# SCH_BusTemp_2026-09-07.net
KiCad netlist of a schematic drawn in EasyEDA
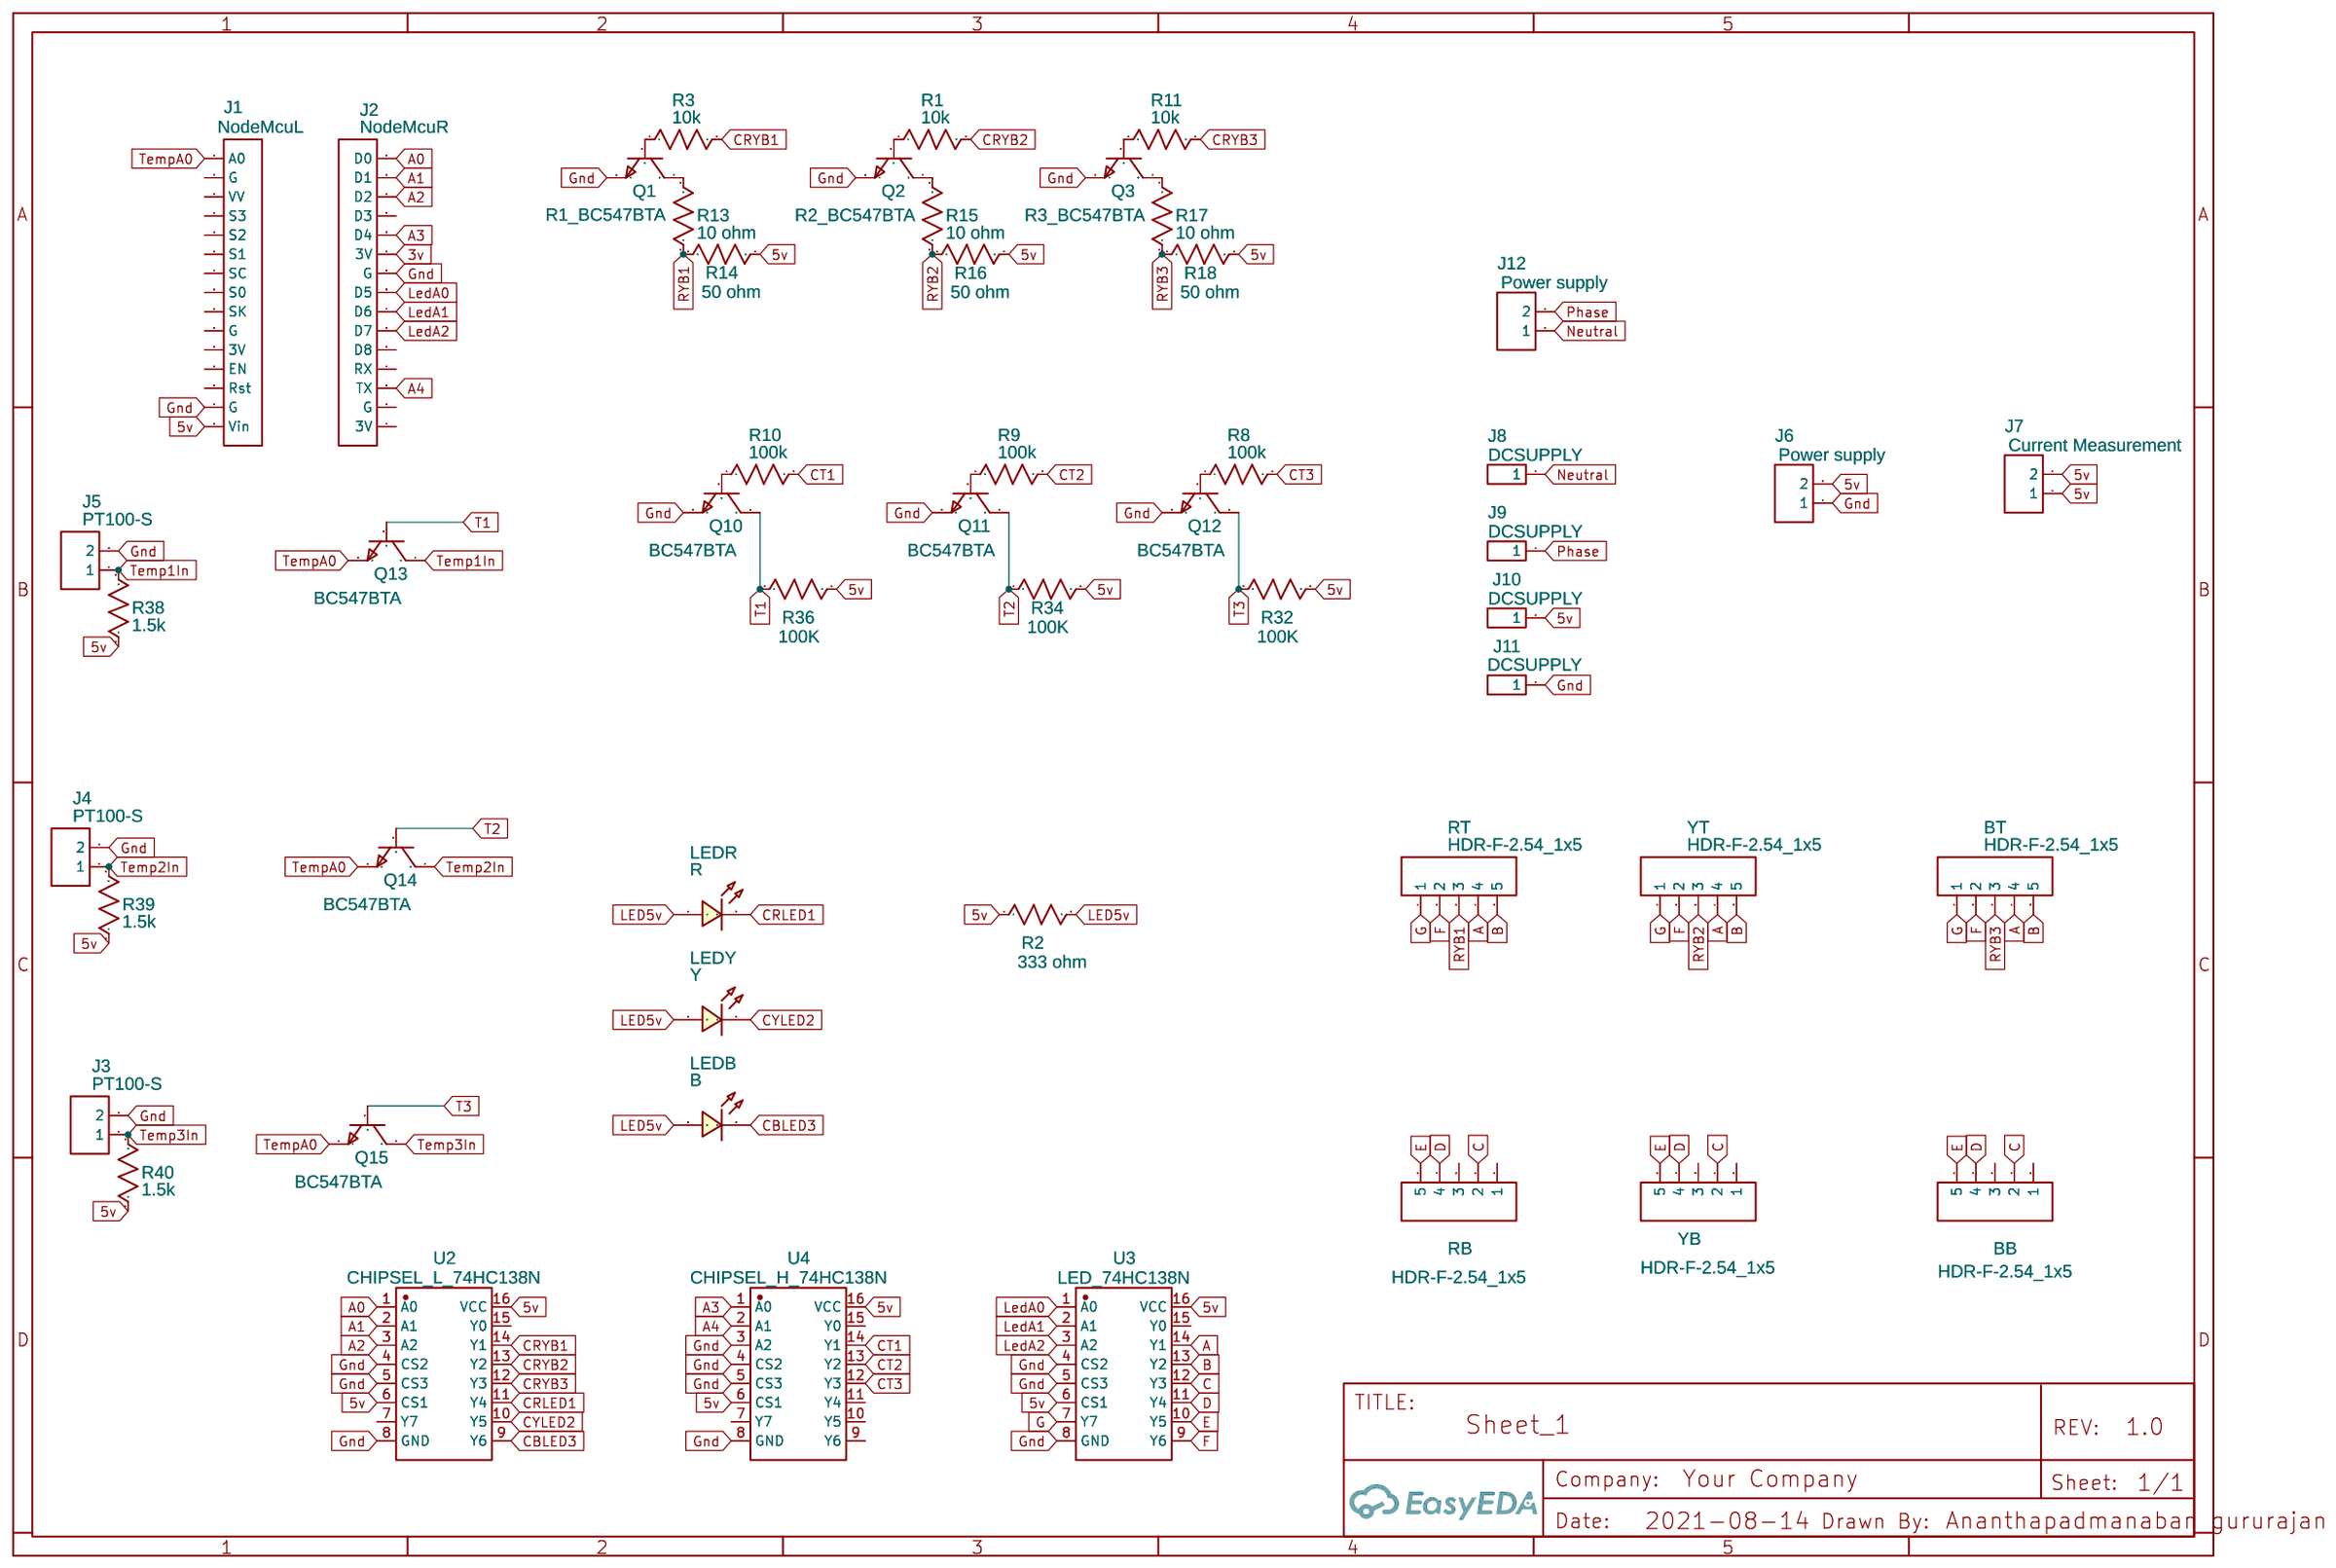
[diagram p0: schematic sheet]

(export (version "E")
  (design (tool "Eeschema 10.0.6"))
  (components
    (comp (ref "BB") (value "HDR-F-2.54_1x5") (libsource (lib "") (part "HDR-F-2.54_1x5_4")))
    (comp (ref "BT") (value "HDR-F-2.54_1x5") (libsource (lib "") (part "HDR-F-2.54_1x5_3")))
    (comp (ref "J1") (value "NodeMcuL") (libsource (lib "") (part "HDR-M-2.54_1x15_1")))
    (comp (ref "J2") (value "NodeMcuR") (libsource (lib "") (part "HDR-M-2.54_1x15")))
    (comp (ref "J3") (value "PT100-S") (libsource (lib "") (part "HDR-M-2.54_1x2")))
    (comp (ref "J4") (value "PT100-S") (libsource (lib "") (part "HDR-M-2.54_1x2")))
    (comp (ref "J5") (value "PT100-S") (libsource (lib "") (part "HDR-M-2.54_1x2")))
    (comp (ref "J6") (value "Power supply") (libsource (lib "") (part "HDR-M-2.54_1x2")))
    (comp (ref "J7") (value "Current Measurement") (libsource (lib "") (part "HDR-M-2.54_1x2")))
    (comp (ref "J8") (value "DCSUPPLY") (libsource (lib "") (part "HDR-M-2.54_1x1")))
    (comp (ref "J9") (value "DCSUPPLY") (libsource (lib "") (part "HDR-M-2.54_1x1")))
    (comp (ref "J10") (value "DCSUPPLY") (libsource (lib "") (part "HDR-M-2.54_1x1")))
    (comp (ref "J11") (value "DCSUPPLY") (libsource (lib "") (part "HDR-M-2.54_1x1")))
    (comp (ref "J12") (value "Power supply") (libsource (lib "") (part "HDR-M-2.54_1x2")))
    (comp (ref "LEDB")
      (value "B")
      (fields
        (field (name "Manufacturer Part") "204-10SUBC/S400-A4")
        (field (name "Manufacturer") "EVERLIGHT(台湾亿光)")
      )
      (libsource (lib "") (part "LED-TH-3mm_B"))
    )
    (comp (ref "LEDR")
      (value "R")
      (fields
        (field (name "Manufacturer Part") "204-10SDRD/S530-A3-L")
        (field (name "Manufacturer") "EVERLIGHT(台湾亿光)")
      )
      (libsource (lib "") (part "LED-TH-3mm_R"))
    )
    (comp (ref "LEDY")
      (value "Y")
      (fields
        (field (name "Manufacturer Part") "204-10SYGD/S530-E3")
        (field (name "Manufacturer") "EVERLIGHT(台湾亿光)")
      )
      (libsource (lib "") (part "LED-TH-3mm_G"))
    )
    (comp (ref "Q1")
      (value "R1_BC547BTA")
      (fields (field (name "Manufacturer Part") "BC547BTA") (field (name "Manufacturer") "ON Semicon"))
      (libsource (lib "") (part "BC547BTA"))
    )
    (comp (ref "Q2")
      (value "R2_BC547BTA")
      (fields (field (name "Manufacturer Part") "BC547BTA") (field (name "Manufacturer") "ON Semicon"))
      (libsource (lib "") (part "BC547BTA"))
    )
    (comp (ref "Q3")
      (value "R3_BC547BTA")
      (fields (field (name "Manufacturer Part") "BC547BTA") (field (name "Manufacturer") "ON Semicon"))
      (libsource (lib "") (part "BC547BTA"))
    )
    (comp (ref "Q10")
      (value "BC547BTA")
      (fields (field (name "Manufacturer") "ON Semicon"))
      (libsource (lib "") (part "BC547BTA"))
    )
    (comp (ref "Q11")
      (value "BC547BTA")
      (fields (field (name "Manufacturer") "ON Semicon"))
      (libsource (lib "") (part "BC547BTA"))
    )
    (comp (ref "Q12")
      (value "BC547BTA")
      (fields (field (name "Manufacturer") "ON Semicon"))
      (libsource (lib "") (part "BC547BTA"))
    )
    (comp (ref "Q13")
      (value "BC547BTA")
      (fields (field (name "Manufacturer") "ON Semicon"))
      (libsource (lib "") (part "BC547BTA"))
    )
    (comp (ref "Q14")
      (value "BC547BTA")
      (fields (field (name "Manufacturer") "ON Semicon"))
      (libsource (lib "") (part "BC547BTA"))
    )
    (comp (ref "Q15")
      (value "BC547BTA")
      (fields (field (name "Manufacturer") "ON Semicon"))
      (libsource (lib "") (part "BC547BTA"))
    )
    (comp (ref "R1") (value "10k") (libsource (lib "") (part "R_AXIAL-0.3_US")))
    (comp (ref "R2") (value "333 ohm") (libsource (lib "") (part "R_AXIAL-0.3_US")))
    (comp (ref "R3") (value "10k") (libsource (lib "") (part "R_AXIAL-0.3_US")))
    (comp (ref "R8") (value "100k") (libsource (lib "") (part "R_AXIAL-0.3_US")))
    (comp (ref "R9") (value "100k") (libsource (lib "") (part "R_AXIAL-0.3_US")))
    (comp (ref "R10") (value "100k") (libsource (lib "") (part "R_AXIAL-0.3_US")))
    (comp (ref "R11") (value "10k") (libsource (lib "") (part "R_AXIAL-0.3_US")))
    (comp (ref "R13") (value "10 ohm") (libsource (lib "") (part "R_AXIAL-0.3_US_1")))
    (comp (ref "R14") (value "50 ohm") (libsource (lib "") (part "R_AXIAL-0.3_US")))
    (comp (ref "R15") (value "10 ohm") (libsource (lib "") (part "R_AXIAL-0.3_US_1")))
    (comp (ref "R16") (value "50 ohm") (libsource (lib "") (part "R_AXIAL-0.3_US")))
    (comp (ref "R17") (value "10 ohm") (libsource (lib "") (part "R_AXIAL-0.3_US_1")))
    (comp (ref "R18") (value "50 ohm") (libsource (lib "") (part "R_AXIAL-0.3_US")))
    (comp (ref "R32") (value "100K") (libsource (lib "") (part "R_AXIAL-0.3_US")))
    (comp (ref "R34") (value "100K") (libsource (lib "") (part "R_AXIAL-0.3_US")))
    (comp (ref "R36") (value "100K") (libsource (lib "") (part "R_AXIAL-0.3_US")))
    (comp (ref "R38") (value "1.5k") (libsource (lib "") (part "R_AXIAL-0.3_US_1")))
    (comp (ref "R39") (value "1.5k") (libsource (lib "") (part "R_AXIAL-0.3_US_1")))
    (comp (ref "R40") (value "1.5k") (libsource (lib "") (part "R_AXIAL-0.3_US_1")))
    (comp (ref "RB") (value "HDR-F-2.54_1x5") (libsource (lib "") (part "HDR-F-2.54_1x5_1")))
    (comp (ref "RT") (value "HDR-F-2.54_1x5") (libsource (lib "") (part "HDR-F-2.54_1x5")))
    (comp (ref "U2")
      (value "CHIPSEL_L_74HC138N")
      (fields (field (name "Manufacturer Part") "74HC138N") (field (name "Manufacturer") "HGSEMI"))
      (libsource (lib "") (part "74HC138N"))
    )
    (comp (ref "U3")
      (value "LED_74HC138N")
      (fields (field (name "Manufacturer Part") "74HC138N") (field (name "Manufacturer") "HGSEMI"))
      (libsource (lib "") (part "74HC138N"))
    )
    (comp (ref "U4")
      (value "CHIPSEL_H_74HC138N")
      (fields (field (name "Manufacturer Part") "74HC138N") (field (name "Manufacturer") "HGSEMI"))
      (libsource (lib "") (part "74HC138N"))
    )
    (comp (ref "YB") (value "HDR-F-2.54_1x5") (libsource (lib "") (part "HDR-F-2.54_1x5_2")))
    (comp (ref "YT") (value "HDR-F-2.54_1x5") (libsource (lib "") (part "HDR-F-2.54_1x5_5")))
  )
  (nets
    (net (code "1") (name "3v") (class "Default")
      (node (ref "J2") (pin "10") (pinfunction "3V_10") (pintype "unspecified"))
    )
    (net (code "2") (name "5v") (class "Default")
      (node (ref "J1") (pin "15") (pinfunction "Vin_15") (pintype "unspecified"))
      (node (ref "J10") (pin "1") (pinfunction "1_1") (pintype "input"))
      (node (ref "J6") (pin "2") (pinfunction "2_2") (pintype "unspecified"))
      (node (ref "J7") (pin "1") (pinfunction "1_1") (pintype "unspecified"))
      (node (ref "J7") (pin "2") (pinfunction "2_2") (pintype "unspecified"))
      (node (ref "R14") (pin "2") (pinfunction "2_2") (pintype "unspecified"))
      (node (ref "R16") (pin "2") (pinfunction "2_2") (pintype "unspecified"))
      (node (ref "R18") (pin "2") (pinfunction "2_2") (pintype "unspecified"))
      (node (ref "R2") (pin "1") (pinfunction "1_1") (pintype "unspecified"))
      (node (ref "R32") (pin "2") (pinfunction "2_2") (pintype "unspecified"))
      (node (ref "R34") (pin "2") (pinfunction "2_2") (pintype "unspecified"))
      (node (ref "R36") (pin "2") (pinfunction "2_2") (pintype "unspecified"))
      (node (ref "R38") (pin "1") (pinfunction "1_1") (pintype "unspecified"))
      (node (ref "R39") (pin "1") (pinfunction "1_1") (pintype "unspecified"))
      (node (ref "R40") (pin "1") (pinfunction "1_1") (pintype "unspecified"))
      (node (ref "U2") (pin "16") (pinfunction "VCC_16") (pintype "unspecified"))
      (node (ref "U2") (pin "6") (pinfunction "CS1_6") (pintype "unspecified"))
      (node (ref "U3") (pin "16") (pinfunction "VCC_16") (pintype "unspecified"))
      (node (ref "U3") (pin "6") (pinfunction "CS1_6") (pintype "unspecified"))
      (node (ref "U4") (pin "16") (pinfunction "VCC_16") (pintype "unspecified"))
      (node (ref "U4") (pin "6") (pinfunction "CS1_6") (pintype "unspecified"))
    )
    (net (code "3") (name "A") (class "Default")
      (node (ref "BT") (pin "4") (pinfunction "4_4") (pintype "unspecified"))
      (node (ref "RT") (pin "4") (pinfunction "4_4") (pintype "unspecified"))
      (node (ref "U3") (pin "14") (pinfunction "Y1_14") (pintype "unspecified"))
      (node (ref "YT") (pin "4") (pinfunction "4_4") (pintype "unspecified"))
    )
    (net (code "4") (name "A0") (class "Default")
      (node (ref "J2") (pin "15") (pinfunction "D0_15") (pintype "unspecified"))
      (node (ref "U2") (pin "1") (pinfunction "A0_1") (pintype "unspecified"))
    )
    (net (code "5") (name "A1") (class "Default")
      (node (ref "J2") (pin "14") (pinfunction "D1_14") (pintype "unspecified"))
      (node (ref "U2") (pin "2") (pinfunction "A1_2") (pintype "unspecified"))
    )
    (net (code "6") (name "A2") (class "Default")
      (node (ref "J2") (pin "13") (pinfunction "D2_13") (pintype "unspecified"))
      (node (ref "U2") (pin "3") (pinfunction "A2_3") (pintype "unspecified"))
    )
    (net (code "7") (name "A3") (class "Default")
      (node (ref "J2") (pin "11") (pinfunction "D4_11") (pintype "unspecified"))
      (node (ref "U4") (pin "1") (pinfunction "A0_1") (pintype "unspecified"))
    )
    (net (code "8") (name "A4") (class "Default")
      (node (ref "J2") (pin "3") (pinfunction "TX_3") (pintype "unspecified"))
      (node (ref "U4") (pin "2") (pinfunction "A1_2") (pintype "unspecified"))
    )
    (net (code "9") (name "B") (class "Default")
      (node (ref "BT") (pin "5") (pinfunction "5_5") (pintype "unspecified"))
      (node (ref "RT") (pin "5") (pinfunction "5_5") (pintype "unspecified"))
      (node (ref "U3") (pin "13") (pinfunction "Y2_13") (pintype "unspecified"))
      (node (ref "YT") (pin "5") (pinfunction "5_5") (pintype "unspecified"))
    )
    (net (code "10") (name "C") (class "Default")
      (node (ref "BB") (pin "2") (pinfunction "2_2") (pintype "unspecified"))
      (node (ref "RB") (pin "2") (pinfunction "2_2") (pintype "unspecified"))
      (node (ref "U3") (pin "12") (pinfunction "Y3_12") (pintype "unspecified"))
      (node (ref "YB") (pin "2") (pinfunction "2_2") (pintype "unspecified"))
    )
    (net (code "11") (name "CBLED3") (class "Default")
      (node (ref "LEDB") (pin "2") (pinfunction "2_2") (pintype "unspecified"))
      (node (ref "U2") (pin "9") (pinfunction "Y6_9") (pintype "unspecified"))
    )
    (net (code "12") (name "CRLED1") (class "Default")
      (node (ref "LEDR") (pin "2") (pinfunction "2_2") (pintype "unspecified"))
      (node (ref "U2") (pin "11") (pinfunction "Y4_11") (pintype "unspecified"))
    )
    (net (code "13") (name "CRYB1") (class "Default")
      (node (ref "R3") (pin "2") (pinfunction "2_2") (pintype "unspecified"))
      (node (ref "U2") (pin "14") (pinfunction "Y1_14") (pintype "unspecified"))
    )
    (net (code "14") (name "CRYB2") (class "Default")
      (node (ref "R1") (pin "2") (pinfunction "2_2") (pintype "unspecified"))
      (node (ref "U2") (pin "13") (pinfunction "Y2_13") (pintype "unspecified"))
    )
    (net (code "15") (name "CRYB3") (class "Default")
      (node (ref "R11") (pin "2") (pinfunction "2_2") (pintype "unspecified"))
      (node (ref "U2") (pin "12") (pinfunction "Y3_12") (pintype "unspecified"))
    )
    (net (code "16") (name "CT1") (class "Default")
      (node (ref "R10") (pin "2") (pinfunction "2_2") (pintype "unspecified"))
      (node (ref "U4") (pin "14") (pinfunction "Y1_14") (pintype "unspecified"))
    )
    (net (code "17") (name "CT2") (class "Default")
      (node (ref "R9") (pin "2") (pinfunction "2_2") (pintype "unspecified"))
      (node (ref "U4") (pin "13") (pinfunction "Y2_13") (pintype "unspecified"))
    )
    (net (code "18") (name "CT3") (class "Default")
      (node (ref "R8") (pin "2") (pinfunction "2_2") (pintype "unspecified"))
      (node (ref "U4") (pin "12") (pinfunction "Y3_12") (pintype "unspecified"))
    )
    (net (code "19") (name "CYLED2") (class "Default")
      (node (ref "LEDY") (pin "2") (pinfunction "2_2") (pintype "unspecified"))
      (node (ref "U2") (pin "10") (pinfunction "Y5_10") (pintype "unspecified"))
    )
    (net (code "20") (name "D") (class "Default")
      (node (ref "BB") (pin "4") (pinfunction "4_4") (pintype "unspecified"))
      (node (ref "RB") (pin "4") (pinfunction "4_4") (pintype "unspecified"))
      (node (ref "U3") (pin "11") (pinfunction "Y4_11") (pintype "unspecified"))
      (node (ref "YB") (pin "4") (pinfunction "4_4") (pintype "unspecified"))
    )
    (net (code "21") (name "E") (class "Default")
      (node (ref "BB") (pin "5") (pinfunction "5_5") (pintype "unspecified"))
      (node (ref "RB") (pin "5") (pinfunction "5_5") (pintype "unspecified"))
      (node (ref "U3") (pin "10") (pinfunction "Y5_10") (pintype "unspecified"))
      (node (ref "YB") (pin "5") (pinfunction "5_5") (pintype "unspecified"))
    )
    (net (code "22") (name "F") (class "Default")
      (node (ref "BT") (pin "2") (pinfunction "2_2") (pintype "unspecified"))
      (node (ref "RT") (pin "2") (pinfunction "2_2") (pintype "unspecified"))
      (node (ref "U3") (pin "9") (pinfunction "Y6_9") (pintype "unspecified"))
      (node (ref "YT") (pin "2") (pinfunction "2_2") (pintype "unspecified"))
    )
    (net (code "23") (name "G") (class "Default")
      (node (ref "BT") (pin "1") (pinfunction "1_1") (pintype "unspecified"))
      (node (ref "RT") (pin "1") (pinfunction "1_1") (pintype "unspecified"))
      (node (ref "U3") (pin "7") (pinfunction "Y7_7") (pintype "unspecified"))
      (node (ref "YT") (pin "1") (pinfunction "1_1") (pintype "unspecified"))
    )
    (net (code "24") (name "Gnd") (class "Default")
      (node (ref "J1") (pin "14") (pinfunction "G_14") (pintype "unspecified"))
      (node (ref "J11") (pin "1") (pinfunction "1_1") (pintype "input"))
      (node (ref "J2") (pin "9") (pinfunction "G_9") (pintype "unspecified"))
      (node (ref "J3") (pin "2") (pinfunction "2_2") (pintype "unspecified"))
      (node (ref "J4") (pin "2") (pinfunction "2_2") (pintype "unspecified"))
      (node (ref "J5") (pin "2") (pinfunction "2_2") (pintype "unspecified"))
      (node (ref "J6") (pin "1") (pinfunction "1_1") (pintype "unspecified"))
      (node (ref "Q1") (pin "3") (pinfunction "E_3") (pintype "unspecified"))
      (node (ref "Q10") (pin "3") (pinfunction "E_3") (pintype "unspecified"))
      (node (ref "Q11") (pin "3") (pinfunction "E_3") (pintype "unspecified"))
      (node (ref "Q12") (pin "3") (pinfunction "E_3") (pintype "unspecified"))
      (node (ref "Q2") (pin "3") (pinfunction "E_3") (pintype "unspecified"))
      (node (ref "Q3") (pin "3") (pinfunction "E_3") (pintype "unspecified"))
      (node (ref "U2") (pin "4") (pinfunction "CS2_4") (pintype "unspecified"))
      (node (ref "U2") (pin "5") (pinfunction "CS3_5") (pintype "unspecified"))
      (node (ref "U2") (pin "8") (pinfunction "GND_8") (pintype "unspecified"))
      (node (ref "U3") (pin "4") (pinfunction "CS2_4") (pintype "unspecified"))
      (node (ref "U3") (pin "5") (pinfunction "CS3_5") (pintype "unspecified"))
      (node (ref "U3") (pin "8") (pinfunction "GND_8") (pintype "unspecified"))
      (node (ref "U4") (pin "3") (pinfunction "A2_3") (pintype "unspecified"))
      (node (ref "U4") (pin "4") (pinfunction "CS2_4") (pintype "unspecified"))
      (node (ref "U4") (pin "5") (pinfunction "CS3_5") (pintype "unspecified"))
      (node (ref "U4") (pin "8") (pinfunction "GND_8") (pintype "unspecified"))
    )
    (net (code "25") (name "LED5v") (class "Default")
      (node (ref "LEDB") (pin "1") (pinfunction "1_1") (pintype "unspecified"))
      (node (ref "LEDR") (pin "1") (pinfunction "1_1") (pintype "unspecified"))
      (node (ref "LEDY") (pin "1") (pinfunction "1_1") (pintype "unspecified"))
      (node (ref "R2") (pin "2") (pinfunction "2_2") (pintype "unspecified"))
    )
    (net (code "26") (name "LedA0") (class "Default")
      (node (ref "J2") (pin "8") (pinfunction "D5_8") (pintype "unspecified"))
      (node (ref "U3") (pin "1") (pinfunction "A0_1") (pintype "unspecified"))
    )
    (net (code "27") (name "LedA1") (class "Default")
      (node (ref "J2") (pin "7") (pinfunction "D6_7") (pintype "unspecified"))
      (node (ref "U3") (pin "2") (pinfunction "A1_2") (pintype "unspecified"))
    )
    (net (code "28") (name "LedA2") (class "Default")
      (node (ref "J2") (pin "6") (pinfunction "D7_6") (pintype "unspecified"))
      (node (ref "U3") (pin "3") (pinfunction "A2_3") (pintype "unspecified"))
    )
    (net (code "29") (name "Net-(Q1-B)") (class "Default")
      (node (ref "Q1") (pin "2") (pinfunction "B_2") (pintype "unspecified"))
      (node (ref "R3") (pin "1") (pinfunction "1_1") (pintype "unspecified"))
    )
    (net (code "30") (name "Net-(Q1-C)") (class "Default")
      (node (ref "Q1") (pin "1") (pinfunction "C_1") (pintype "unspecified"))
      (node (ref "R13") (pin "2") (pinfunction "2_2") (pintype "unspecified"))
    )
    (net (code "31") (name "Net-(Q2-B)") (class "Default")
      (node (ref "Q2") (pin "2") (pinfunction "B_2") (pintype "unspecified"))
      (node (ref "R1") (pin "1") (pinfunction "1_1") (pintype "unspecified"))
    )
    (net (code "32") (name "Net-(Q2-C)") (class "Default")
      (node (ref "Q2") (pin "1") (pinfunction "C_1") (pintype "unspecified"))
      (node (ref "R15") (pin "2") (pinfunction "2_2") (pintype "unspecified"))
    )
    (net (code "33") (name "Net-(Q3-B)") (class "Default")
      (node (ref "Q3") (pin "2") (pinfunction "B_2") (pintype "unspecified"))
      (node (ref "R11") (pin "1") (pinfunction "1_1") (pintype "unspecified"))
    )
    (net (code "34") (name "Net-(Q3-C)") (class "Default")
      (node (ref "Q3") (pin "1") (pinfunction "C_1") (pintype "unspecified"))
      (node (ref "R17") (pin "2") (pinfunction "2_2") (pintype "unspecified"))
    )
    (net (code "35") (name "Net-(Q10-B)") (class "Default")
      (node (ref "Q10") (pin "2") (pinfunction "B_2") (pintype "unspecified"))
      (node (ref "R10") (pin "1") (pinfunction "1_1") (pintype "unspecified"))
    )
    (net (code "36") (name "Net-(Q11-B)") (class "Default")
      (node (ref "Q11") (pin "2") (pinfunction "B_2") (pintype "unspecified"))
      (node (ref "R9") (pin "1") (pinfunction "1_1") (pintype "unspecified"))
    )
    (net (code "37") (name "Net-(Q12-B)") (class "Default")
      (node (ref "Q12") (pin "2") (pinfunction "B_2") (pintype "unspecified"))
      (node (ref "R8") (pin "1") (pinfunction "1_1") (pintype "unspecified"))
    )
    (net (code "38") (name "Neutral") (class "Default")
      (node (ref "J12") (pin "1") (pinfunction "1_1") (pintype "unspecified"))
      (node (ref "J8") (pin "1") (pinfunction "1_1") (pintype "input"))
    )
    (net (code "39") (name "Phase") (class "Default")
      (node (ref "J12") (pin "2") (pinfunction "2_2") (pintype "unspecified"))
      (node (ref "J9") (pin "1") (pinfunction "1_1") (pintype "input"))
    )
    (net (code "40") (name "RYB1") (class "Default")
      (node (ref "R13") (pin "1") (pinfunction "1_1") (pintype "unspecified"))
      (node (ref "R14") (pin "1") (pinfunction "1_1") (pintype "unspecified"))
      (node (ref "RT") (pin "3") (pinfunction "3_3") (pintype "unspecified"))
    )
    (net (code "41") (name "RYB2") (class "Default")
      (node (ref "R15") (pin "1") (pinfunction "1_1") (pintype "unspecified"))
      (node (ref "R16") (pin "1") (pinfunction "1_1") (pintype "unspecified"))
      (node (ref "YT") (pin "3") (pinfunction "3_3") (pintype "unspecified"))
    )
    (net (code "42") (name "RYB3") (class "Default")
      (node (ref "BT") (pin "3") (pinfunction "3_3") (pintype "unspecified"))
      (node (ref "R17") (pin "1") (pinfunction "1_1") (pintype "unspecified"))
      (node (ref "R18") (pin "1") (pinfunction "1_1") (pintype "unspecified"))
    )
    (net (code "43") (name "T1") (class "Default")
      (node (ref "Q10") (pin "1") (pinfunction "C_1") (pintype "unspecified"))
      (node (ref "Q13") (pin "2") (pinfunction "B_2") (pintype "unspecified"))
      (node (ref "R36") (pin "1") (pinfunction "1_1") (pintype "unspecified"))
    )
    (net (code "44") (name "T2") (class "Default")
      (node (ref "Q11") (pin "1") (pinfunction "C_1") (pintype "unspecified"))
      (node (ref "Q14") (pin "2") (pinfunction "B_2") (pintype "unspecified"))
      (node (ref "R34") (pin "1") (pinfunction "1_1") (pintype "unspecified"))
    )
    (net (code "45") (name "T3") (class "Default")
      (node (ref "Q12") (pin "1") (pinfunction "C_1") (pintype "unspecified"))
      (node (ref "Q15") (pin "2") (pinfunction "B_2") (pintype "unspecified"))
      (node (ref "R32") (pin "1") (pinfunction "1_1") (pintype "unspecified"))
    )
    (net (code "46") (name "Temp1In") (class "Default")
      (node (ref "J5") (pin "1") (pinfunction "1_1") (pintype "unspecified"))
      (node (ref "Q13") (pin "1") (pinfunction "C_1") (pintype "unspecified"))
      (node (ref "R38") (pin "2") (pinfunction "2_2") (pintype "unspecified"))
    )
    (net (code "47") (name "Temp2In") (class "Default")
      (node (ref "J4") (pin "1") (pinfunction "1_1") (pintype "unspecified"))
      (node (ref "Q14") (pin "1") (pinfunction "C_1") (pintype "unspecified"))
      (node (ref "R39") (pin "2") (pinfunction "2_2") (pintype "unspecified"))
    )
    (net (code "48") (name "Temp3In") (class "Default")
      (node (ref "J3") (pin "1") (pinfunction "1_1") (pintype "unspecified"))
      (node (ref "Q15") (pin "1") (pinfunction "C_1") (pintype "unspecified"))
      (node (ref "R40") (pin "2") (pinfunction "2_2") (pintype "unspecified"))
    )
    (net (code "49") (name "TempA0") (class "Default")
      (node (ref "J1") (pin "1") (pinfunction "A0_1") (pintype "unspecified"))
      (node (ref "Q13") (pin "3") (pinfunction "E_3") (pintype "unspecified"))
      (node (ref "Q14") (pin "3") (pinfunction "E_3") (pintype "unspecified"))
      (node (ref "Q15") (pin "3") (pinfunction "E_3") (pintype "unspecified"))
    )
    (net (code "50") (name "unconnected-(BB-Pad1)") (class "Default")
      (node (ref "BB") (pin "1") (pinfunction "1_1") (pintype "unspecified"))
    )
    (net (code "51") (name "unconnected-(BB-Pad3)") (class "Default")
      (node (ref "BB") (pin "3") (pinfunction "3_3") (pintype "unspecified"))
    )
    (net (code "52") (name "unconnected-(J1-3V-Pad11)") (class "Default")
      (node (ref "J1") (pin "11") (pinfunction "3V_11") (pintype "unspecified"))
    )
    (net (code "53") (name "unconnected-(J1-EN-Pad12)") (class "Default")
      (node (ref "J1") (pin "12") (pinfunction "EN_12") (pintype "unspecified"))
    )
    (net (code "54") (name "unconnected-(J1-G-Pad2)") (class "Default")
      (node (ref "J1") (pin "2") (pinfunction "G_2") (pintype "unspecified"))
    )
    (net (code "55") (name "unconnected-(J1-G-Pad10)") (class "Default")
      (node (ref "J1") (pin "10") (pinfunction "G_10") (pintype "unspecified"))
    )
    (net (code "56") (name "unconnected-(J1-Rst-Pad13)") (class "Default")
      (node (ref "J1") (pin "13") (pinfunction "Rst_13") (pintype "unspecified"))
    )
    (net (code "57") (name "unconnected-(J1-S0-Pad8)") (class "Default")
      (node (ref "J1") (pin "8") (pinfunction "S0_8") (pintype "unspecified"))
    )
    (net (code "58") (name "unconnected-(J1-S1-Pad6)") (class "Default")
      (node (ref "J1") (pin "6") (pinfunction "S1_6") (pintype "unspecified"))
    )
    (net (code "59") (name "unconnected-(J1-S2-Pad5)") (class "Default")
      (node (ref "J1") (pin "5") (pinfunction "S2_5") (pintype "unspecified"))
    )
    (net (code "60") (name "unconnected-(J1-S3-Pad4)") (class "Default")
      (node (ref "J1") (pin "4") (pinfunction "S3_4") (pintype "unspecified"))
    )
    (net (code "61") (name "unconnected-(J1-SC-Pad7)") (class "Default")
      (node (ref "J1") (pin "7") (pinfunction "SC_7") (pintype "unspecified"))
    )
    (net (code "62") (name "unconnected-(J1-SK-Pad9)") (class "Default")
      (node (ref "J1") (pin "9") (pinfunction "SK_9") (pintype "unspecified"))
    )
    (net (code "63") (name "unconnected-(J1-VV-Pad3)") (class "Default")
      (node (ref "J1") (pin "3") (pinfunction "VV_3") (pintype "unspecified"))
    )
    (net (code "64") (name "unconnected-(J2-3V-Pad1)") (class "Default")
      (node (ref "J2") (pin "1") (pinfunction "3V_1") (pintype "unspecified"))
    )
    (net (code "65") (name "unconnected-(J2-D3-Pad12)") (class "Default")
      (node (ref "J2") (pin "12") (pinfunction "D3_12") (pintype "unspecified"))
    )
    (net (code "66") (name "unconnected-(J2-D8-Pad5)") (class "Default")
      (node (ref "J2") (pin "5") (pinfunction "D8_5") (pintype "unspecified"))
    )
    (net (code "67") (name "unconnected-(J2-G-Pad2)") (class "Default")
      (node (ref "J2") (pin "2") (pinfunction "G_2") (pintype "unspecified"))
    )
    (net (code "68") (name "unconnected-(J2-RX-Pad4)") (class "Default")
      (node (ref "J2") (pin "4") (pinfunction "RX_4") (pintype "unspecified"))
    )
    (net (code "69") (name "unconnected-(RB-Pad1)") (class "Default")
      (node (ref "RB") (pin "1") (pinfunction "1_1") (pintype "unspecified"))
    )
    (net (code "70") (name "unconnected-(RB-Pad3)") (class "Default")
      (node (ref "RB") (pin "3") (pinfunction "3_3") (pintype "unspecified"))
    )
    (net (code "71") (name "unconnected-(U2-Y0-Pad15)") (class "Default")
      (node (ref "U2") (pin "15") (pinfunction "Y0_15") (pintype "unspecified"))
    )
    (net (code "72") (name "unconnected-(U2-Y7-Pad7)") (class "Default")
      (node (ref "U2") (pin "7") (pinfunction "Y7_7") (pintype "unspecified"))
    )
    (net (code "73") (name "unconnected-(U3-Y0-Pad15)") (class "Default")
      (node (ref "U3") (pin "15") (pinfunction "Y0_15") (pintype "unspecified"))
    )
    (net (code "74") (name "unconnected-(U4-Y0-Pad15)") (class "Default")
      (node (ref "U4") (pin "15") (pinfunction "Y0_15") (pintype "unspecified"))
    )
    (net (code "75") (name "unconnected-(U4-Y4-Pad11)") (class "Default")
      (node (ref "U4") (pin "11") (pinfunction "Y4_11") (pintype "unspecified"))
    )
    (net (code "76") (name "unconnected-(U4-Y5-Pad10)") (class "Default")
      (node (ref "U4") (pin "10") (pinfunction "Y5_10") (pintype "unspecified"))
    )
    (net (code "77") (name "unconnected-(U4-Y6-Pad9)") (class "Default")
      (node (ref "U4") (pin "9") (pinfunction "Y6_9") (pintype "unspecified"))
    )
    (net (code "78") (name "unconnected-(U4-Y7-Pad7)") (class "Default")
      (node (ref "U4") (pin "7") (pinfunction "Y7_7") (pintype "unspecified"))
    )
    (net (code "79") (name "unconnected-(YB-Pad1)") (class "Default")
      (node (ref "YB") (pin "1") (pinfunction "1_1") (pintype "unspecified"))
    )
    (net (code "80") (name "unconnected-(YB-Pad3)") (class "Default")
      (node (ref "YB") (pin "3") (pinfunction "3_3") (pintype "unspecified"))
    )
  )
)
